# CanTransceiver.net
KiCad netlist of a schematic drawn in Altium Designer
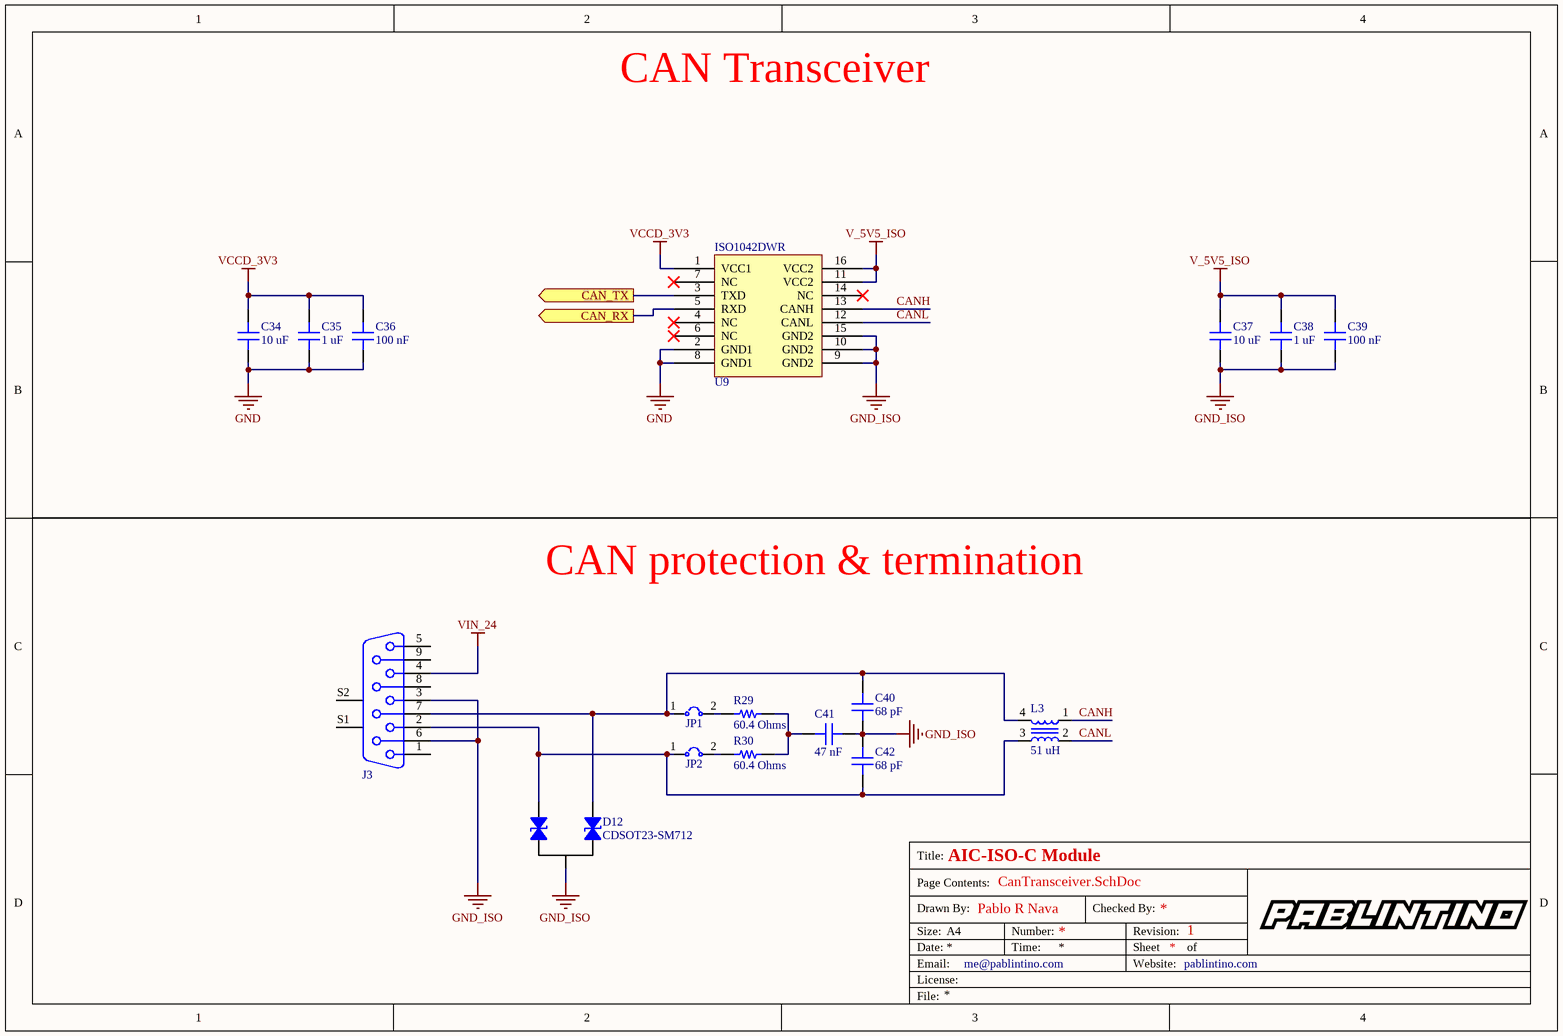
[diagram p0: CanTransceiver.SchDoc]

(export (version "E")
  (design (tool "Eeschema 10.0.6"))
  (components
    (comp (ref "C34")
      (value "10 uF")
      (footprint "CAP 0805_2012")
      (description "MLCC Ceramic 10 uF 25 V 20% Capacitor")
      (fields (field (name "PART NUMBER") "0805YC106MAT2A") (field (name "MANUFACTURER") "AVX"))
      (libsource (lib "Database_Libs") (part "Capacitor"))
    )
    (comp (ref "C35")
      (value "1 uF")
      (footprint "CAP 0603_1608")
      (description "MLCC Ceramic 1 uF 25 V 10% Capacitor")
      (fields (field (name "PART NUMBER") "06033C105KAT4A") (field (name "MANUFACTURER") "AVX"))
      (libsource (lib "Database_Libs") (part "Capacitor"))
    )
    (comp (ref "C36")
      (value "100 nF")
      (footprint "CAP 0603_1608")
      (description "MLCC Ceramic 100 nF 50 V 10% Capacitor")
      (fields (field (name "PART NUMBER") "06035C104K4Z2A") (field (name "MANUFACTURER") "AVX"))
      (libsource (lib "Database_Libs") (part "Capacitor"))
    )
    (comp (ref "C37")
      (value "10 uF")
      (footprint "CAP 0805_2012")
      (description "MLCC Ceramic 10 uF 25 V 20% Capacitor")
      (fields (field (name "PART NUMBER") "0805YC106MAT2A") (field (name "MANUFACTURER") "AVX"))
      (libsource (lib "Database_Libs") (part "Capacitor"))
    )
    (comp (ref "C38")
      (value "1 uF")
      (footprint "CAP 0603_1608")
      (description "MLCC Ceramic 1 uF 25 V 10% Capacitor")
      (fields (field (name "PART NUMBER") "06033C105KAT4A") (field (name "MANUFACTURER") "AVX"))
      (libsource (lib "Database_Libs") (part "Capacitor"))
    )
    (comp (ref "C39")
      (value "100 nF")
      (footprint "CAP 0603_1608")
      (description "MLCC Ceramic 100 nF 50 V 10% Capacitor")
      (fields (field (name "PART NUMBER") "06035C104K4Z2A") (field (name "MANUFACTURER") "AVX"))
      (libsource (lib "Database_Libs") (part "Capacitor"))
    )
    (comp (ref "C40")
      (value "68 pF")
      (footprint "CAP 0603_1608")
      (description "MLCC Ceramic 68 pF 100 V 2% Capacitor")
      (fields (field (name "PART NUMBER") "06031U680GAT2A") (field (name "MANUFACTURER") "AVX"))
      (libsource (lib "Database_Libs") (part "Capacitor"))
    )
    (comp (ref "C41")
      (value "47 nF")
      (footprint "CAP 0805_2012")
      (description "MLCC Ceramic 47 nF 100 V 10% Capacitor")
      (fields (field (name "PART NUMBER") "C2012X7R2A473K125AA") (field (name "MANUFACTURER") "TDK"))
      (libsource (lib "Database_Libs") (part "Capacitor"))
    )
    (comp (ref "C42")
      (value "68 pF")
      (footprint "CAP 0603_1608")
      (description "MLCC Ceramic 68 pF 100 V 2% Capacitor")
      (fields (field (name "PART NUMBER") "06031U680GAT2A") (field (name "MANUFACTURER") "AVX"))
      (libsource (lib "Database_Libs") (part "Capacitor"))
    )
    (comp (ref "D12")
      (value "CDSOT23-SM712")
      (footprint "BOURNS SOT-23-3")
      (description "CAN bus TVS diode")
      (fields (field (name "MANUFACTURER") "Bourns"))
      (libsource (lib "Database_Libs") (part "DUAL TVS"))
    )
    (comp (ref "J3")
      (value "09681537613")
      (footprint "DSUB9")
      (description "DSUB SV FE SSDP ANG-US 09P AU3")
      (fields (field (name "MANUFACTURER") "Harting"))
      (libsource (lib "Database_Libs") (part "D Connector 9"))
    )
    (comp (ref "JP1")
      (value "61300211121")
      (footprint "JUMPER-100")
      (description "Connector Header Through Hole 2 position 0.100 (2.54mm)")
      (fields (field (name "MANUFACTURER") "Würth Elektronik"))
      (libsource (lib "Database_Libs") (part "JUMPER"))
    )
    (comp (ref "JP2")
      (value "61300211121")
      (footprint "JUMPER-100")
      (description "Connector Header Through Hole 2 position 0.100 (2.54mm)")
      (fields (field (name "MANUFACTURER") "Würth Elektronik"))
      (libsource (lib "Database_Libs") (part "JUMPER"))
    )
    (comp (ref "L3")
      (value "51 uH")
      (footprint "TDK_ACT45B")
      (description "CAN Bus Common Choke")
      (fields (field (name "PART NUMBER") "ACT45B-510-2P-TL003") (field (name "MANUFACTURER") "TDK"))
      (libsource (lib "Database_Libs") (part "Inductor"))
    )
    (comp (ref "R29")
      (value "60.4 Ohms")
      (footprint "RES 0805_2012")
      (description "Thin Film Resistor 60.4 Ohms 1%")
      (fields (field (name "PART NUMBER") "CRCW080560R4FKEA") (field (name "MANUFACTURER") "Vishay / Dale"))
      (libsource (lib "Database_Libs") (part "Resistor"))
    )
    (comp (ref "R30")
      (value "60.4 Ohms")
      (footprint "RES 0805_2012")
      (description "Thin Film Resistor 60.4 Ohms 1%")
      (fields (field (name "PART NUMBER") "CRCW080560R4FKEA") (field (name "MANUFACTURER") "Vishay / Dale"))
      (libsource (lib "Database_Libs") (part "Resistor"))
    )
    (comp (ref "U9")
      (value "ISO1042DWR")
      (footprint "TI-DW16_N")
      (description "Isolated CAN FD Transceiver")
      (fields (field (name "MANUFACTURER") "Texas Instruments"))
      (libsource (lib "Database_Libs") (part "ISO1042"))
    )
  )
  (nets
    (net (code "1") (name "/CANH") (class "Default")
      (node (ref "L3") (pin "1") (pinfunction "1_1") (pintype "passive"))
      (node (ref "U9") (pin "13") (pinfunction "CANH_13") (pintype "passive"))
    )
    (net (code "2") (name "/CANL") (class "Default")
      (node (ref "L3") (pin "2") (pinfunction "2_2") (pintype "passive"))
      (node (ref "U9") (pin "12") (pinfunction "CANL_12") (pintype "passive"))
    )
    (net (code "3") (name "/CAN_RX") (class "Default")
      (node (ref "U9") (pin "5") (pinfunction "RXD_5") (pintype "passive"))
    )
    (net (code "4") (name "/CAN_TX") (class "Default")
      (node (ref "U9") (pin "3") (pinfunction "TXD_3") (pintype "passive"))
    )
    (net (code "5") (name "GND") (class "Default")
      (node (ref "C34") (pin "2") (pinfunction "2_2") (pintype "passive"))
      (node (ref "C35") (pin "1") (pinfunction "1_1") (pintype "passive"))
      (node (ref "C36") (pin "2") (pinfunction "2_2") (pintype "passive"))
      (node (ref "U9") (pin "2") (pinfunction "GND1_2") (pintype "passive"))
      (node (ref "U9") (pin "8") (pinfunction "GND1_8") (pintype "passive"))
    )
    (net (code "6") (name "GND_ISO") (class "Default")
      (node (ref "C37") (pin "2") (pinfunction "2_2") (pintype "passive"))
      (node (ref "C38") (pin "1") (pinfunction "1_1") (pintype "passive"))
      (node (ref "C39") (pin "2") (pinfunction "2_2") (pintype "passive"))
      (node (ref "C40") (pin "2") (pinfunction "2_2") (pintype "passive"))
      (node (ref "C41") (pin "1") (pinfunction "1_1") (pintype "passive"))
      (node (ref "C42") (pin "1") (pinfunction "1_1") (pintype "passive"))
      (node (ref "D12") (pin "3") (pinfunction "3_3") (pintype "passive"))
      (node (ref "J3") (pin "3") (pinfunction "3_3") (pintype "passive"))
      (node (ref "J3") (pin "6") (pinfunction "6_6") (pintype "passive"))
      (node (ref "U9") (pin "10") (pinfunction "GND2_10") (pintype "passive"))
      (node (ref "U9") (pin "15") (pinfunction "GND2_15") (pintype "passive"))
      (node (ref "U9") (pin "9") (pinfunction "GND2_9") (pintype "passive"))
    )
    (net (code "7") (name "Net-(C41-Pad2)") (class "Default")
      (node (ref "C41") (pin "2") (pinfunction "2_2") (pintype "passive"))
      (node (ref "R29") (pin "1") (pinfunction "1_1") (pintype "passive"))
      (node (ref "R30") (pin "1") (pinfunction "1_1") (pintype "passive"))
    )
    (net (code "8") (name "Net-(JP1-A)") (class "Default")
      (node (ref "C40") (pin "1") (pinfunction "1_1") (pintype "passive"))
      (node (ref "D12") (pin "2") (pinfunction "2_2") (pintype "passive"))
      (node (ref "J3") (pin "7") (pinfunction "7_7") (pintype "passive"))
      (node (ref "JP1") (pin "1") (pinfunction "A_1") (pintype "passive"))
      (node (ref "L3") (pin "4") (pinfunction "4_4") (pintype "passive"))
    )
    (net (code "9") (name "Net-(JP1-K)") (class "Default")
      (node (ref "JP1") (pin "2") (pinfunction "K_2") (pintype "passive"))
      (node (ref "R29") (pin "2") (pinfunction "2_2") (pintype "passive"))
    )
    (net (code "10") (name "Net-(JP2-A)") (class "Default")
      (node (ref "C42") (pin "2") (pinfunction "2_2") (pintype "passive"))
      (node (ref "D12") (pin "1") (pinfunction "1_1") (pintype "passive"))
      (node (ref "J3") (pin "2") (pinfunction "2_2") (pintype "passive"))
      (node (ref "JP2") (pin "1") (pinfunction "A_1") (pintype "passive"))
      (node (ref "L3") (pin "3") (pinfunction "3_3") (pintype "passive"))
    )
    (net (code "11") (name "Net-(JP2-K)") (class "Default")
      (node (ref "JP2") (pin "2") (pinfunction "K_2") (pintype "passive"))
      (node (ref "R30") (pin "2") (pinfunction "2_2") (pintype "passive"))
    )
    (net (code "12") (name "VCCD_3V3") (class "Default")
      (node (ref "C34") (pin "1") (pinfunction "1_1") (pintype "passive"))
      (node (ref "C35") (pin "2") (pinfunction "2_2") (pintype "passive"))
      (node (ref "C36") (pin "1") (pinfunction "1_1") (pintype "passive"))
      (node (ref "U9") (pin "1") (pinfunction "VCC1_1") (pintype "passive"))
    )
    (net (code "13") (name "VIN_24") (class "Default")
      (node (ref "J3") (pin "4") (pinfunction "4_4") (pintype "passive"))
    )
    (net (code "14") (name "V_5V5_ISO") (class "Default")
      (node (ref "C37") (pin "1") (pinfunction "1_1") (pintype "passive"))
      (node (ref "C38") (pin "2") (pinfunction "2_2") (pintype "passive"))
      (node (ref "C39") (pin "1") (pinfunction "1_1") (pintype "passive"))
      (node (ref "U9") (pin "11") (pinfunction "VCC2_11") (pintype "passive"))
      (node (ref "U9") (pin "16") (pinfunction "VCC2_16") (pintype "passive"))
    )
    (net (code "15") (name "unconnected-(J3-Pad1)") (class "Default")
      (node (ref "J3") (pin "1") (pinfunction "1_1") (pintype "passive"))
    )
    (net (code "16") (name "unconnected-(J3-Pad5)") (class "Default")
      (node (ref "J3") (pin "5") (pinfunction "5_5") (pintype "passive"))
    )
    (net (code "17") (name "unconnected-(J3-Pad8)") (class "Default")
      (node (ref "J3") (pin "8") (pinfunction "8_8") (pintype "passive"))
    )
    (net (code "18") (name "unconnected-(J3-Pad9)") (class "Default")
      (node (ref "J3") (pin "9") (pinfunction "9_9") (pintype "passive"))
    )
    (net (code "19") (name "unconnected-(J3-PadS1)") (class "Default")
      (node (ref "J3") (pin "S1") (pinfunction "S1_S1") (pintype "passive"))
    )
    (net (code "20") (name "unconnected-(J3-PadS2)") (class "Default")
      (node (ref "J3") (pin "S2") (pinfunction "S2_S2") (pintype "passive"))
    )
    (net (code "21") (name "unconnected-(U9-NC-Pad4)") (class "Default")
      (node (ref "U9") (pin "4") (pinfunction "NC_4") (pintype "passive+no_connect"))
    )
    (net (code "22") (name "unconnected-(U9-NC-Pad6)") (class "Default")
      (node (ref "U9") (pin "6") (pinfunction "NC_6") (pintype "passive+no_connect"))
    )
    (net (code "23") (name "unconnected-(U9-NC-Pad7)") (class "Default")
      (node (ref "U9") (pin "7") (pinfunction "NC_7") (pintype "passive+no_connect"))
    )
    (net (code "24") (name "unconnected-(U9-NC-Pad14)") (class "Default")
      (node (ref "U9") (pin "14") (pinfunction "NC_14") (pintype "passive+no_connect"))
    )
  )
)
